# cheapboard1_1qfn.net
KiCad netlist of a schematic drawn in EAGLE
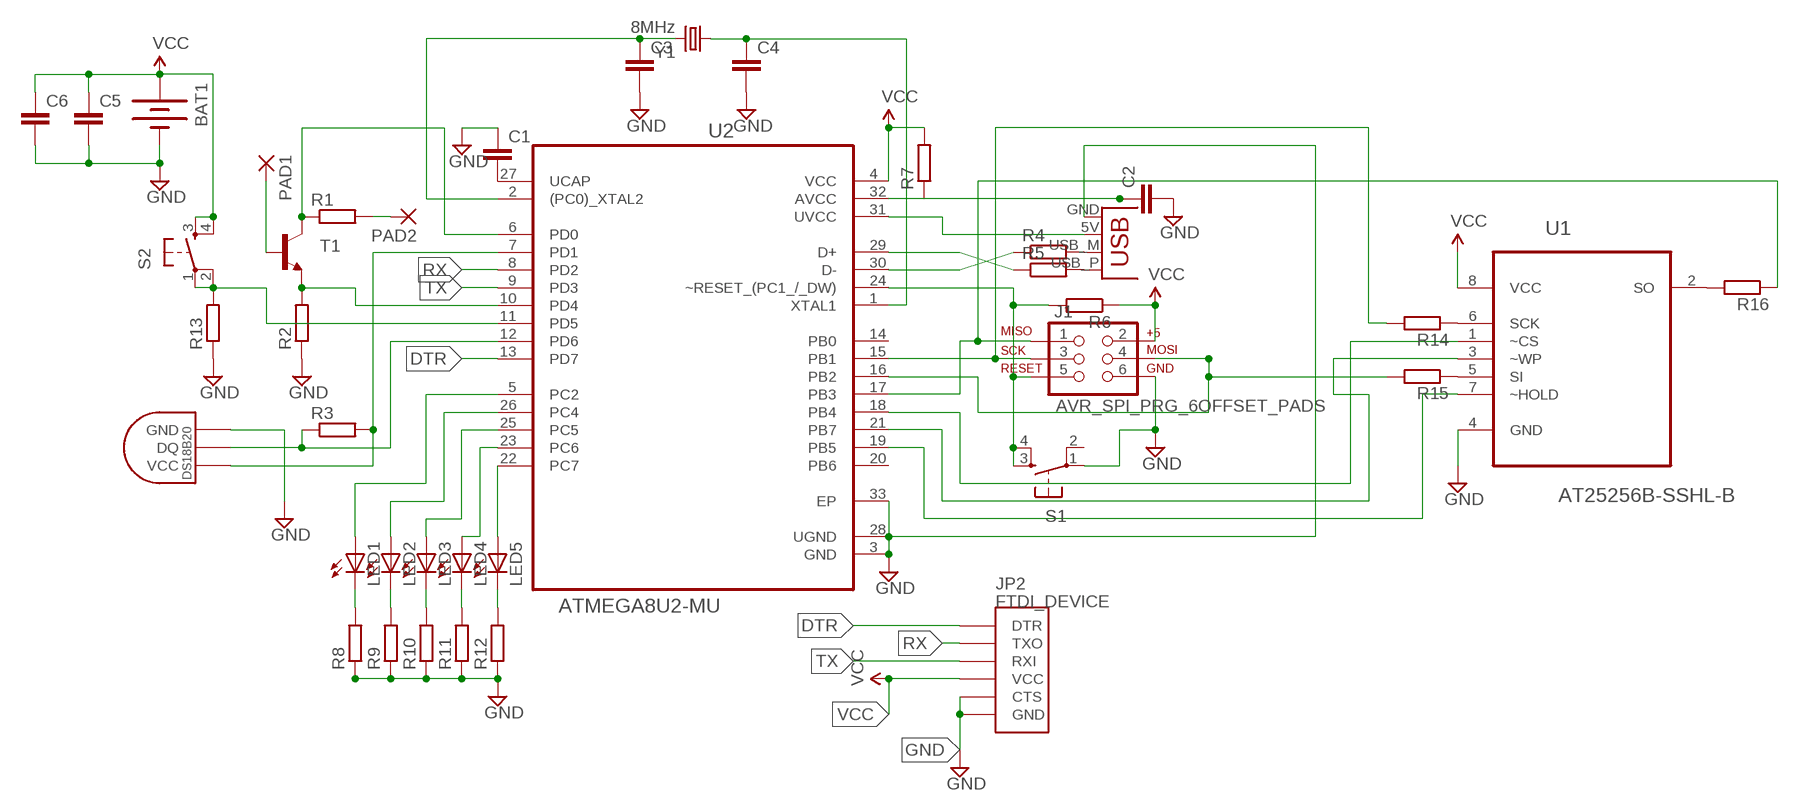
[diagram p0: schematic, sheet 1]

(export (version "E")
  (design (tool "Eeschema 10.0.6"))
  (components
    (comp (ref "BAT1")
      (value "BATTERY245PTH")
      (footprint "eagle-import:BATTCON_245MM_PTH")
      (libsource (lib "eagle-import") (part "BATTERY245PTH"))
    )
    (comp (ref "C1")
      (value "CAP0805")
      (footprint "eagle-import:0805")
      (libsource (lib "eagle-import") (part "CAP0805"))
    )
    (comp (ref "C2")
      (value "CAP0805")
      (footprint "eagle-import:0805")
      (libsource (lib "eagle-import") (part "CAP0805"))
    )
    (comp (ref "C3")
      (value "CAP0805")
      (footprint "eagle-import:0805")
      (libsource (lib "eagle-import") (part "CAP0805"))
    )
    (comp (ref "C4")
      (value "CAP0805")
      (footprint "eagle-import:0805")
      (libsource (lib "eagle-import") (part "CAP0805"))
    )
    (comp (ref "C5")
      (value "CAP0805")
      (footprint "eagle-import:0805")
      (libsource (lib "eagle-import") (part "CAP0805"))
    )
    (comp (ref "C6")
      (value "CAP0805")
      (footprint "eagle-import:0805")
      (libsource (lib "eagle-import") (part "CAP0805"))
    )
    (comp (ref "J1")
      (value "AVR_SPI_PRG_6OFFSET_PADS")
      (footprint "eagle-import:2X3_OFFSET")
      (libsource (lib "eagle-import") (part "AVR_SPI_PRG_6OFFSET_PADS"))
    )
    (comp (ref "JP1")
      (value "USBPCB")
      (footprint "eagle-import:USB-A-PCB")
      (libsource (lib "eagle-import") (part "USBPCB"))
    )
    (comp (ref "JP2")
      (value "FTDI_DEVICE")
      (footprint "eagle-import:FTDI_DEVICE_SIDE")
      (libsource (lib "eagle-import") (part "FTDI_DEVICE"))
    )
    (comp (ref "LED1")
      (value "LEDCHIPLED_0805")
      (footprint "eagle-import:CHIPLED_0805")
      (libsource (lib "eagle-import") (part "LEDCHIPLED_0805"))
    )
    (comp (ref "LED2")
      (value "LEDCHIPLED_0805")
      (footprint "eagle-import:CHIPLED_0805")
      (libsource (lib "eagle-import") (part "LEDCHIPLED_0805"))
    )
    (comp (ref "LED3")
      (value "LEDCHIPLED_0805")
      (footprint "eagle-import:CHIPLED_0805")
      (libsource (lib "eagle-import") (part "LEDCHIPLED_0805"))
    )
    (comp (ref "LED4")
      (value "LEDCHIPLED_0805")
      (footprint "eagle-import:CHIPLED_0805")
      (libsource (lib "eagle-import") (part "LEDCHIPLED_0805"))
    )
    (comp (ref "LED5")
      (value "LEDCHIPLED_0805")
      (footprint "eagle-import:CHIPLED_0805")
      (libsource (lib "eagle-import") (part "LEDCHIPLED_0805"))
    )
    (comp (ref "PAD1")
      (value "SMD5")
      (footprint "eagle-import:SMD2,54-5,08")
      (libsource (lib "eagle-import") (part "SMD5"))
    )
    (comp (ref "PAD2")
      (value "SMD5")
      (footprint "eagle-import:SMD2,54-5,08")
      (libsource (lib "eagle-import") (part "SMD5"))
    )
    (comp (ref "R1")
      (value "R-EU_M0805")
      (footprint "eagle-import:M0805")
      (libsource (lib "eagle-import") (part "R-EU_M0805"))
    )
    (comp (ref "R2")
      (value "R-EU_M0805")
      (footprint "eagle-import:M0805")
      (libsource (lib "eagle-import") (part "R-EU_M0805"))
    )
    (comp (ref "R3")
      (value "R-EU_M0805")
      (footprint "eagle-import:M0805")
      (libsource (lib "eagle-import") (part "R-EU_M0805"))
    )
    (comp (ref "R4")
      (value "R-EU_M0805")
      (footprint "eagle-import:M0805")
      (libsource (lib "eagle-import") (part "R-EU_M0805"))
    )
    (comp (ref "R5")
      (value "R-EU_M0805")
      (footprint "eagle-import:M0805")
      (libsource (lib "eagle-import") (part "R-EU_M0805"))
    )
    (comp (ref "R6")
      (value "R-EU_M0805")
      (footprint "eagle-import:M0805")
      (libsource (lib "eagle-import") (part "R-EU_M0805"))
    )
    (comp (ref "R7")
      (value "R-EU_M0805")
      (footprint "eagle-import:M0805")
      (libsource (lib "eagle-import") (part "R-EU_M0805"))
    )
    (comp (ref "R8")
      (value "R-EU_M0805")
      (footprint "eagle-import:M0805")
      (libsource (lib "eagle-import") (part "R-EU_M0805"))
    )
    (comp (ref "R9")
      (value "R-EU_M0805")
      (footprint "eagle-import:M0805")
      (libsource (lib "eagle-import") (part "R-EU_M0805"))
    )
    (comp (ref "R10")
      (value "R-EU_M0805")
      (footprint "eagle-import:M0805")
      (libsource (lib "eagle-import") (part "R-EU_M0805"))
    )
    (comp (ref "R11")
      (value "R-EU_M0805")
      (footprint "eagle-import:M0805")
      (libsource (lib "eagle-import") (part "R-EU_M0805"))
    )
    (comp (ref "R12")
      (value "R-EU_M0805")
      (footprint "eagle-import:M0805")
      (libsource (lib "eagle-import") (part "R-EU_M0805"))
    )
    (comp (ref "R13")
      (value "R-EU_M0805")
      (footprint "eagle-import:M0805")
      (libsource (lib "eagle-import") (part "R-EU_M0805"))
    )
    (comp (ref "R14")
      (value "R-EU_M0805")
      (footprint "eagle-import:M0805")
      (libsource (lib "eagle-import") (part "R-EU_M0805"))
    )
    (comp (ref "R15")
      (value "R-EU_M0805")
      (footprint "eagle-import:M0805")
      (libsource (lib "eagle-import") (part "R-EU_M0805"))
    )
    (comp (ref "R16")
      (value "R-EU_M0805")
      (footprint "eagle-import:M0805")
      (libsource (lib "eagle-import") (part "R-EU_M0805"))
    )
    (comp (ref "S1")
      (value "TAC_SWITCHSMD")
      (footprint "eagle-import:TACTILE_SWITCH_SMD")
      (libsource (lib "eagle-import") (part "TAC_SWITCHSMD"))
    )
    (comp (ref "S2")
      (value "TAC_SWITCHSMD")
      (footprint "eagle-import:TACTILE_SWITCH_SMD")
      (libsource (lib "eagle-import") (part "TAC_SWITCHSMD"))
    )
    (comp (ref "T1")
      (value "TRANSISTOR_NPNSOT23-3")
      (footprint "eagle-import:SOT23-3")
      (libsource (lib "eagle-import") (part "TRANSISTOR_NPNSOT23-3"))
    )
    (comp (ref "U$1")
      (value "DS1820SOIC")
      (footprint "eagle-import:DS18B20_SOIC")
      (libsource (lib "eagle-import") (part "DS1820SOIC"))
    )
    (comp (ref "U1")
      (value "AT25256B-SSHL-B")
      (footprint "eagle-import:SOIC127P600X175-8N")
      (libsource (lib "eagle-import") (part "AT25256B-SSHL-B"))
    )
    (comp (ref "U2")
      (value "ATMEGA8U2-MU")
      (footprint "eagle-import:QFN50P500X500X100-33N")
      (libsource (lib "eagle-import") (part "ATMEGA8U2-MU"))
    )
    (comp (ref "Y1")
      (value "8MHz")
      (footprint "eagle-import:CRYSTAL-SMD-5X3")
      (libsource (lib "eagle-import") (part "CRYSTAL5X3"))
    )
  )
  (nets
    (net (code "1") (name "DTR") (class "Default")
      (node (ref "JP2") (pin "P$1") (pinfunction "DTR_P$1") (pintype "bidirectional"))
      (node (ref "U2") (pin "13") (pinfunction "PD7_13") (pintype "bidirectional"))
    )
    (net (code "2") (name "GND") (class "Default")
      (node (ref "BAT1") (pin "2") (pinfunction "-_2") (pintype "power_in"))
      (node (ref "C1") (pin "1") (pinfunction "1_1") (pintype "passive"))
      (node (ref "C2") (pin "2") (pinfunction "2_2") (pintype "passive"))
      (node (ref "C3") (pin "2") (pinfunction "2_2") (pintype "passive"))
      (node (ref "C4") (pin "2") (pinfunction "2_2") (pintype "passive"))
      (node (ref "C5") (pin "2") (pinfunction "2_2") (pintype "passive"))
      (node (ref "C6") (pin "2") (pinfunction "2_2") (pintype "passive"))
      (node (ref "J1") (pin "6") (pinfunction "6_6") (pintype "passive"))
      (node (ref "JP1") (pin "GND") (pinfunction "GND_GND") (pintype "bidirectional"))
      (node (ref "JP2") (pin "P$5") (pinfunction "CTS_P$5") (pintype "bidirectional"))
      (node (ref "JP2") (pin "P$6") (pinfunction "GND_P$6") (pintype "bidirectional"))
      (node (ref "R10") (pin "1") (pinfunction "1_1") (pintype "passive"))
      (node (ref "R11") (pin "1") (pinfunction "1_1") (pintype "passive"))
      (node (ref "R12") (pin "1") (pinfunction "1_1") (pintype "passive"))
      (node (ref "R13") (pin "1") (pinfunction "1_1") (pintype "passive"))
      (node (ref "R2") (pin "1") (pinfunction "1_1") (pintype "passive"))
      (node (ref "R8") (pin "1") (pinfunction "1_1") (pintype "passive"))
      (node (ref "R9") (pin "1") (pinfunction "1_1") (pintype "passive"))
      (node (ref "S1") (pin "1") (pinfunction "1_1") (pintype "passive"))
      (node (ref "U$1") (pin "GND") (pinfunction "GND_GND") (pintype "power_in"))
      (node (ref "U1") (pin "4") (pinfunction "GND_4") (pintype "passive"))
      (node (ref "U2") (pin "28") (pinfunction "UGND_28") (pintype "passive"))
      (node (ref "U2") (pin "3") (pinfunction "GND_3") (pintype "passive"))
      (node (ref "U2") (pin "33") (pinfunction "EP_33") (pintype "passive"))
    )
    (net (code "3") (name "Net-(JP1-D+)") (class "Default")
      (node (ref "JP1") (pin "USB_P") (pinfunction "D+_USB_P") (pintype "bidirectional"))
      (node (ref "R5") (pin "2") (pinfunction "2_2") (pintype "passive"))
    )
    (net (code "4") (name "Net-(JP1-D-)") (class "Default")
      (node (ref "JP1") (pin "USB_M") (pinfunction "D-_USB_M") (pintype "bidirectional"))
      (node (ref "R4") (pin "2") (pinfunction "2_2") (pintype "passive"))
    )
    (net (code "5") (name "Net-(JP1-VBUS)") (class "Default")
      (node (ref "JP1") (pin "5V") (pinfunction "VBUS_5V") (pintype "bidirectional"))
      (node (ref "U2") (pin "31") (pinfunction "UVCC_31") (pintype "power_in"))
    )
    (net (code "6") (name "Net-(LED1-PadC)") (class "Default")
      (node (ref "LED1") (pin "C") (pinfunction "C_C") (pintype "passive"))
      (node (ref "R8") (pin "2") (pinfunction "2_2") (pintype "passive"))
    )
    (net (code "7") (name "Net-(LED2-PadC)") (class "Default")
      (node (ref "LED2") (pin "C") (pinfunction "C_C") (pintype "passive"))
      (node (ref "R9") (pin "2") (pinfunction "2_2") (pintype "passive"))
    )
    (net (code "8") (name "Net-(LED3-PadC)") (class "Default")
      (node (ref "LED3") (pin "C") (pinfunction "C_C") (pintype "passive"))
      (node (ref "R10") (pin "2") (pinfunction "2_2") (pintype "passive"))
    )
    (net (code "9") (name "Net-(LED4-PadC)") (class "Default")
      (node (ref "LED4") (pin "C") (pinfunction "C_C") (pintype "passive"))
      (node (ref "R11") (pin "2") (pinfunction "2_2") (pintype "passive"))
    )
    (net (code "10") (name "Net-(LED5-PadC)") (class "Default")
      (node (ref "LED5") (pin "C") (pinfunction "C_C") (pintype "passive"))
      (node (ref "R12") (pin "2") (pinfunction "2_2") (pintype "passive"))
    )
    (net (code "11") (name "Net-(PAD1-P)") (class "Default")
      (node (ref "PAD1") (pin "1") (pinfunction "P_1") (pintype "passive"))
      (node (ref "T1") (pin "1") (pinfunction "B_1") (pintype "passive"))
    )
    (net (code "12") (name "Net-(PAD2-P)") (class "Default")
      (node (ref "PAD2") (pin "1") (pinfunction "P_1") (pintype "passive"))
      (node (ref "R1") (pin "2") (pinfunction "2_2") (pintype "passive"))
    )
    (net (code "13") (name "Net-(T1-C)") (class "Default")
      (node (ref "R1") (pin "1") (pinfunction "1_1") (pintype "passive"))
      (node (ref "T1") (pin "3") (pinfunction "C_3") (pintype "passive"))
      (node (ref "U2") (pin "6") (pinfunction "PD0_6") (pintype "bidirectional"))
    )
    (net (code "14") (name "Net-(T1-E)") (class "Default")
      (node (ref "R2") (pin "2") (pinfunction "2_2") (pintype "passive"))
      (node (ref "T1") (pin "2") (pinfunction "E_2") (pintype "passive"))
      (node (ref "U2") (pin "10") (pinfunction "PD4_10") (pintype "bidirectional"))
    )
    (net (code "15") (name "Net-(U1-SCK)") (class "Default")
      (node (ref "R14") (pin "1") (pinfunction "1_1") (pintype "passive"))
      (node (ref "U1") (pin "6") (pinfunction "SCK_6") (pintype "input"))
    )
    (net (code "16") (name "Net-(U1-SI)") (class "Default")
      (node (ref "R15") (pin "1") (pinfunction "1_1") (pintype "passive"))
      (node (ref "U1") (pin "5") (pinfunction "SI_5") (pintype "input"))
    )
    (net (code "17") (name "Net-(U1-SO)") (class "Default")
      (node (ref "R16") (pin "2") (pinfunction "2_2") (pintype "passive"))
      (node (ref "U1") (pin "2") (pinfunction "SO_2") (pintype "output"))
    )
    (net (code "18") (name "Net-(U1-~{CS})") (class "Default")
      (node (ref "U1") (pin "1") (pinfunction "~{CS}_1") (pintype "input"))
      (node (ref "U2") (pin "18") (pinfunction "PB4_18") (pintype "bidirectional"))
    )
    (net (code "19") (name "Net-(U1-~{HOLD})") (class "Default")
      (node (ref "U1") (pin "7") (pinfunction "~{HOLD}_7") (pintype "input"))
      (node (ref "U2") (pin "19") (pinfunction "PB5_19") (pintype "bidirectional"))
    )
    (net (code "20") (name "Net-(U1-~{WP})") (class "Default")
      (node (ref "U1") (pin "3") (pinfunction "~{WP}_3") (pintype "input"))
      (node (ref "U2") (pin "21") (pinfunction "PB7_21") (pintype "bidirectional"))
    )
    (net (code "21") (name "Net-(U2-(PC0)_XTAL2)") (class "Default")
      (node (ref "C3") (pin "1") (pinfunction "1_1") (pintype "passive"))
      (node (ref "U2") (pin "2") (pinfunction "(PC0)_XTAL2_2") (pintype "bidirectional"))
      (node (ref "Y1") (pin "3") (pinfunction "2_3") (pintype "passive"))
    )
    (net (code "22") (name "Net-(U2-AVCC)") (class "Default")
      (node (ref "C2") (pin "1") (pinfunction "1_1") (pintype "passive"))
      (node (ref "R7") (pin "1") (pinfunction "1_1") (pintype "passive"))
      (node (ref "U2") (pin "32") (pinfunction "AVCC_32") (pintype "power_in"))
    )
    (net (code "23") (name "Net-(U2-D+)") (class "Default")
      (node (ref "R5") (pin "1") (pinfunction "1_1") (pintype "passive"))
      (node (ref "U2") (pin "29") (pinfunction "D+_29") (pintype "passive"))
    )
    (net (code "24") (name "Net-(U2-D-)") (class "Default")
      (node (ref "R4") (pin "1") (pinfunction "1_1") (pintype "passive"))
      (node (ref "U2") (pin "30") (pinfunction "D-_30") (pintype "passive"))
    )
    (net (code "25") (name "Net-(U2-PB1)") (class "Default")
      (node (ref "J1") (pin "3") (pinfunction "3_3") (pintype "passive"))
      (node (ref "R14") (pin "2") (pinfunction "2_2") (pintype "passive"))
      (node (ref "U2") (pin "15") (pinfunction "PB1_15") (pintype "bidirectional"))
    )
    (net (code "26") (name "Net-(U2-PB2)") (class "Default")
      (node (ref "J1") (pin "4") (pinfunction "4_4") (pintype "passive"))
      (node (ref "R15") (pin "2") (pinfunction "2_2") (pintype "passive"))
      (node (ref "U2") (pin "16") (pinfunction "PB2_16") (pintype "bidirectional"))
    )
    (net (code "27") (name "Net-(U2-PB3)") (class "Default")
      (node (ref "J1") (pin "1") (pinfunction "1_1") (pintype "passive"))
      (node (ref "R16") (pin "1") (pinfunction "1_1") (pintype "passive"))
      (node (ref "U2") (pin "17") (pinfunction "PB3_17") (pintype "bidirectional"))
    )
    (net (code "28") (name "Net-(U2-PC2)") (class "Default")
      (node (ref "LED1") (pin "A") (pinfunction "A_A") (pintype "passive"))
      (node (ref "U2") (pin "5") (pinfunction "PC2_5") (pintype "bidirectional"))
    )
    (net (code "29") (name "Net-(U2-PC4)") (class "Default")
      (node (ref "LED2") (pin "A") (pinfunction "A_A") (pintype "passive"))
      (node (ref "U2") (pin "26") (pinfunction "PC4_26") (pintype "bidirectional"))
    )
    (net (code "30") (name "Net-(U2-PC5)") (class "Default")
      (node (ref "LED3") (pin "A") (pinfunction "A_A") (pintype "passive"))
      (node (ref "U2") (pin "25") (pinfunction "PC5_25") (pintype "bidirectional"))
    )
    (net (code "31") (name "Net-(U2-PC6)") (class "Default")
      (node (ref "LED4") (pin "A") (pinfunction "A_A") (pintype "passive"))
      (node (ref "U2") (pin "23") (pinfunction "PC6_23") (pintype "bidirectional"))
    )
    (net (code "32") (name "Net-(U2-PC7)") (class "Default")
      (node (ref "LED5") (pin "A") (pinfunction "A_A") (pintype "passive"))
      (node (ref "U2") (pin "22") (pinfunction "PC7_22") (pintype "bidirectional"))
    )
    (net (code "33") (name "Net-(U2-PD1)") (class "Default")
      (node (ref "R3") (pin "2") (pinfunction "2_2") (pintype "passive"))
      (node (ref "U$1") (pin "VCC") (pinfunction "VCC_VCC") (pintype "power_in"))
      (node (ref "U2") (pin "7") (pinfunction "PD1_7") (pintype "bidirectional"))
    )
    (net (code "34") (name "Net-(U2-PD5)") (class "Default")
      (node (ref "R13") (pin "2") (pinfunction "2_2") (pintype "passive"))
      (node (ref "S2") (pin "1") (pinfunction "1_1") (pintype "passive"))
      (node (ref "S2") (pin "2") (pinfunction "2_2") (pintype "passive"))
      (node (ref "U2") (pin "11") (pinfunction "PD5_11") (pintype "bidirectional"))
    )
    (net (code "35") (name "Net-(U2-PD6)") (class "Default")
      (node (ref "R3") (pin "1") (pinfunction "1_1") (pintype "passive"))
      (node (ref "U$1") (pin "DQ") (pinfunction "DQ_DQ") (pintype "bidirectional"))
      (node (ref "U2") (pin "12") (pinfunction "PD6_12") (pintype "bidirectional"))
    )
    (net (code "36") (name "Net-(U2-UCAP)") (class "Default")
      (node (ref "C1") (pin "2") (pinfunction "2_2") (pintype "passive"))
      (node (ref "U2") (pin "27") (pinfunction "UCAP_27") (pintype "power_in"))
    )
    (net (code "37") (name "Net-(U2-XTAL1)") (class "Default")
      (node (ref "C4") (pin "1") (pinfunction "1_1") (pintype "passive"))
      (node (ref "U2") (pin "1") (pinfunction "XTAL1_1") (pintype "input"))
      (node (ref "Y1") (pin "1") (pinfunction "1_1") (pintype "passive"))
    )
    (net (code "38") (name "Net-(U2-~{RESET_(PC1_{slash}_DW}))") (class "Default")
      (node (ref "J1") (pin "5") (pinfunction "5_5") (pintype "passive"))
      (node (ref "R6") (pin "2") (pinfunction "2_2") (pintype "passive"))
      (node (ref "S1") (pin "3") (pinfunction "3_3") (pintype "passive"))
      (node (ref "S1") (pin "4") (pinfunction "4_4") (pintype "passive"))
      (node (ref "U2") (pin "24") (pinfunction "~{RESET_(PC1_/_DW})_24") (pintype "bidirectional"))
    )
    (net (code "39") (name "RX") (class "Default")
      (node (ref "JP2") (pin "P$2") (pinfunction "TXO_P$2") (pintype "bidirectional"))
      (node (ref "U2") (pin "8") (pinfunction "PD2_8") (pintype "bidirectional"))
    )
    (net (code "40") (name "TX") (class "Default")
      (node (ref "JP2") (pin "P$3") (pinfunction "RXI_P$3") (pintype "bidirectional"))
      (node (ref "U2") (pin "9") (pinfunction "PD3_9") (pintype "bidirectional"))
    )
    (net (code "41") (name "VCC") (class "Default")
      (node (ref "BAT1") (pin "3") (pinfunction "+_3") (pintype "power_in"))
      (node (ref "C5") (pin "1") (pinfunction "1_1") (pintype "passive"))
      (node (ref "C6") (pin "1") (pinfunction "1_1") (pintype "passive"))
      (node (ref "J1") (pin "2") (pinfunction "2_2") (pintype "passive"))
      (node (ref "JP2") (pin "P$4") (pinfunction "VCC_P$4") (pintype "bidirectional"))
      (node (ref "R6") (pin "1") (pinfunction "1_1") (pintype "passive"))
      (node (ref "R7") (pin "2") (pinfunction "2_2") (pintype "passive"))
      (node (ref "S2") (pin "3") (pinfunction "3_3") (pintype "passive"))
      (node (ref "S2") (pin "4") (pinfunction "4_4") (pintype "passive"))
      (node (ref "U1") (pin "8") (pinfunction "VCC_8") (pintype "power_in"))
      (node (ref "U2") (pin "4") (pinfunction "VCC_4") (pintype "power_in"))
    )
    (net (code "42") (name "unconnected-(S1-Pad2)") (class "Default")
      (node (ref "S1") (pin "2") (pinfunction "2_2") (pintype "passive"))
    )
    (net (code "43") (name "unconnected-(U2-PB0-Pad14)") (class "Default")
      (node (ref "U2") (pin "14") (pinfunction "PB0_14") (pintype "bidirectional"))
    )
    (net (code "44") (name "unconnected-(U2-PB6-Pad20)") (class "Default")
      (node (ref "U2") (pin "20") (pinfunction "PB6_20") (pintype "bidirectional"))
    )
  )
)
